# ADC_inputs.net
KiCad netlist of a schematic drawn in Altium Designer
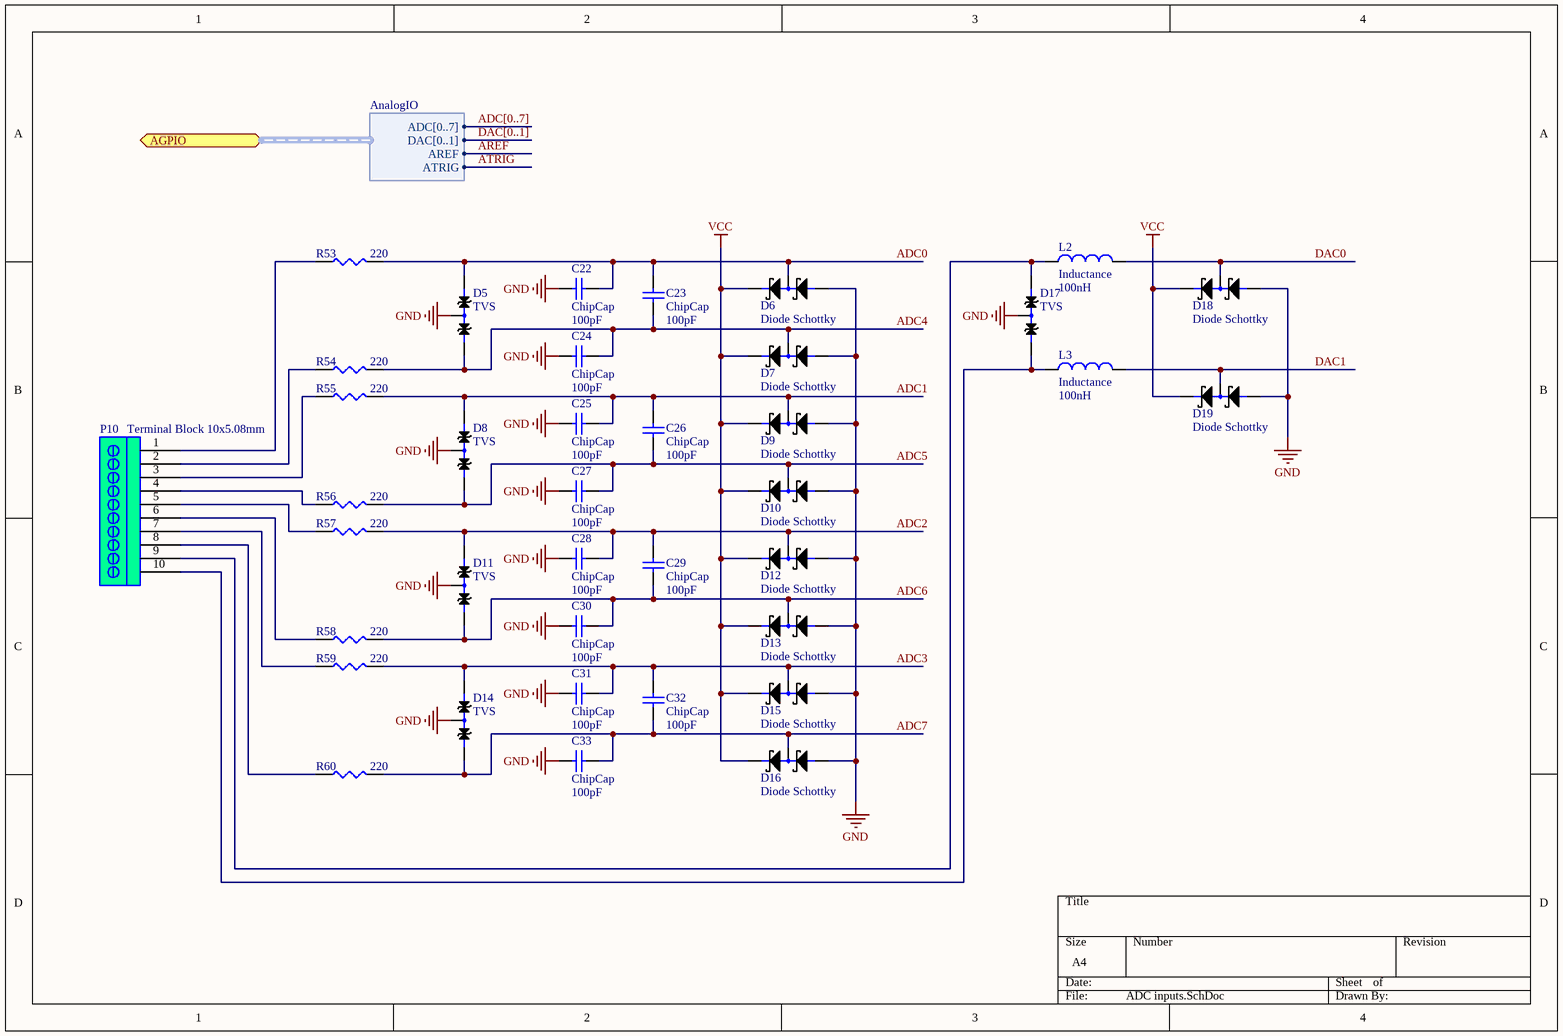
[diagram p0: ADC inputs.SchDoc]

(export (version "E")
  (design (tool "Eeschema 10.0.6"))
  (components
    (comp (ref "C22")
      (value "ChipCap")
      (footprint "CAP0805")
      (description "Capacitor")
      (fields (field (name "ALTIUM_VALUE") "100pF") (field (name "PUBLISHER") "Altium Limited"))
      (libsource (lib "Common Devices") (part "ChipCap"))
    )
    (comp (ref "C23")
      (value "ChipCap")
      (footprint "CAP0805")
      (description "Capacitor")
      (fields (field (name "ALTIUM_VALUE") "100pF") (field (name "PUBLISHER") "Altium Limited"))
      (libsource (lib "Common Devices") (part "ChipCap"))
    )
    (comp (ref "C24")
      (value "ChipCap")
      (footprint "CAP0805")
      (description "Capacitor")
      (fields (field (name "ALTIUM_VALUE") "100pF") (field (name "PUBLISHER") "Altium Limited"))
      (libsource (lib "Common Devices") (part "ChipCap"))
    )
    (comp (ref "C25")
      (value "ChipCap")
      (footprint "CAP0805")
      (description "Capacitor")
      (fields (field (name "ALTIUM_VALUE") "100pF") (field (name "PUBLISHER") "Altium Limited"))
      (libsource (lib "Common Devices") (part "ChipCap"))
    )
    (comp (ref "C26")
      (value "ChipCap")
      (footprint "CAP0805")
      (description "Capacitor")
      (fields (field (name "ALTIUM_VALUE") "100pF") (field (name "PUBLISHER") "Altium Limited"))
      (libsource (lib "Common Devices") (part "ChipCap"))
    )
    (comp (ref "C27")
      (value "ChipCap")
      (footprint "CAP0805")
      (description "Capacitor")
      (fields (field (name "ALTIUM_VALUE") "100pF") (field (name "PUBLISHER") "Altium Limited"))
      (libsource (lib "Common Devices") (part "ChipCap"))
    )
    (comp (ref "C28")
      (value "ChipCap")
      (footprint "CAP0805")
      (description "Capacitor")
      (fields (field (name "ALTIUM_VALUE") "100pF") (field (name "PUBLISHER") "Altium Limited"))
      (libsource (lib "Common Devices") (part "ChipCap"))
    )
    (comp (ref "C29")
      (value "ChipCap")
      (footprint "CAP0805")
      (description "Capacitor")
      (fields (field (name "ALTIUM_VALUE") "100pF") (field (name "PUBLISHER") "Altium Limited"))
      (libsource (lib "Common Devices") (part "ChipCap"))
    )
    (comp (ref "C30")
      (value "ChipCap")
      (footprint "CAP0805")
      (description "Capacitor")
      (fields (field (name "ALTIUM_VALUE") "100pF") (field (name "PUBLISHER") "Altium Limited"))
      (libsource (lib "Common Devices") (part "ChipCap"))
    )
    (comp (ref "C31")
      (value "ChipCap")
      (footprint "CAP0805")
      (description "Capacitor")
      (fields (field (name "ALTIUM_VALUE") "100pF") (field (name "PUBLISHER") "Altium Limited"))
      (libsource (lib "Common Devices") (part "ChipCap"))
    )
    (comp (ref "C32")
      (value "ChipCap")
      (footprint "CAP0805")
      (description "Capacitor")
      (fields (field (name "ALTIUM_VALUE") "100pF") (field (name "PUBLISHER") "Altium Limited"))
      (libsource (lib "Common Devices") (part "ChipCap"))
    )
    (comp (ref "C33")
      (value "ChipCap")
      (footprint "CAP0805")
      (description "Capacitor")
      (fields (field (name "ALTIUM_VALUE") "100pF") (field (name "PUBLISHER") "Altium Limited"))
      (libsource (lib "Common Devices") (part "ChipCap"))
    )
    (comp (ref "D5")
      (value "TVS")
      (footprint "SOT23")
      (description "Dual bidirectional voltage supresor")
      (libsource (lib "Protection") (part "TVS Diode"))
    )
    (comp (ref "D6")
      (value "Diode Schottky")
      (footprint "SOT23")
      (description "2-Diode Schottky")
      (libsource (lib "Protection") (part "Schottky Diode"))
    )
    (comp (ref "D7")
      (value "Diode Schottky")
      (footprint "SOT23")
      (description "2-Diode Schottky")
      (libsource (lib "Protection") (part "Schottky Diode"))
    )
    (comp (ref "D8")
      (value "TVS")
      (footprint "SOT23")
      (description "Dual bidirectional voltage supresor")
      (libsource (lib "Protection") (part "TVS Diode"))
    )
    (comp (ref "D9")
      (value "Diode Schottky")
      (footprint "SOT23")
      (description "2-Diode Schottky")
      (libsource (lib "Protection") (part "Schottky Diode"))
    )
    (comp (ref "D10")
      (value "Diode Schottky")
      (footprint "SOT23")
      (description "2-Diode Schottky")
      (libsource (lib "Protection") (part "Schottky Diode"))
    )
    (comp (ref "D11")
      (value "TVS")
      (footprint "SOT23")
      (description "Dual bidirectional voltage supresor")
      (libsource (lib "Protection") (part "TVS Diode"))
    )
    (comp (ref "D12")
      (value "Diode Schottky")
      (footprint "SOT23")
      (description "2-Diode Schottky")
      (libsource (lib "Protection") (part "Schottky Diode"))
    )
    (comp (ref "D13")
      (value "Diode Schottky")
      (footprint "SOT23")
      (description "2-Diode Schottky")
      (libsource (lib "Protection") (part "Schottky Diode"))
    )
    (comp (ref "D14")
      (value "TVS")
      (footprint "SOT23")
      (description "Dual bidirectional voltage supresor")
      (libsource (lib "Protection") (part "TVS Diode"))
    )
    (comp (ref "D15")
      (value "Diode Schottky")
      (footprint "SOT23")
      (description "2-Diode Schottky")
      (libsource (lib "Protection") (part "Schottky Diode"))
    )
    (comp (ref "D16")
      (value "Diode Schottky")
      (footprint "SOT23")
      (description "2-Diode Schottky")
      (libsource (lib "Protection") (part "Schottky Diode"))
    )
    (comp (ref "D17")
      (value "TVS")
      (footprint "SOT23")
      (description "Dual bidirectional voltage supresor")
      (libsource (lib "Protection") (part "TVS Diode"))
    )
    (comp (ref "D18")
      (value "Diode Schottky")
      (footprint "SOT23")
      (description "2-Diode Schottky")
      (libsource (lib "Protection") (part "Schottky Diode"))
    )
    (comp (ref "D19")
      (value "Diode Schottky")
      (footprint "SOT23")
      (description "2-Diode Schottky")
      (libsource (lib "Protection") (part "Schottky Diode"))
    )
    (comp (ref "L2")
      (value "Inductance")
      (footprint "CM45")
      (fields (field (name "ALTIUM_VALUE") "100nH"))
      (libsource (lib "Common Devices") (part "ChipInductance"))
    )
    (comp (ref "L3")
      (value "Inductance")
      (footprint "CM45")
      (fields (field (name "ALTIUM_VALUE") "100nH"))
      (libsource (lib "Common Devices") (part "ChipInductance"))
    )
    (comp (ref "P10")
      (value "Terminal Block 10x5.08mm")
      (footprint "Socket 10x5.08")
      (description "Terminal Block Socket Right Angle 10x5.08mm 2-Wall")
      (libsource (lib "IndustrialConnectors") (part "Socket_10x5.08_RA_2Wall"))
    )
    (comp (ref "R53")
      (value "220")
      (footprint "RES0805")
      (description "Chip resistor")
      (fields (field (name "Comment") "ChipRes"))
      (libsource (lib "Common Devices") (part "ChipRes"))
    )
    (comp (ref "R54")
      (value "220")
      (footprint "RES0805")
      (description "Chip resistor")
      (fields (field (name "Comment") "ChipRes"))
      (libsource (lib "Common Devices") (part "ChipRes"))
    )
    (comp (ref "R55")
      (value "220")
      (footprint "RES0805")
      (description "Chip resistor")
      (fields (field (name "Comment") "ChipRes"))
      (libsource (lib "Common Devices") (part "ChipRes"))
    )
    (comp (ref "R56")
      (value "220")
      (footprint "RES0805")
      (description "Chip resistor")
      (fields (field (name "Comment") "ChipRes"))
      (libsource (lib "Common Devices") (part "ChipRes"))
    )
    (comp (ref "R57")
      (value "220")
      (footprint "RES0805")
      (description "Chip resistor")
      (fields (field (name "Comment") "ChipRes"))
      (libsource (lib "Common Devices") (part "ChipRes"))
    )
    (comp (ref "R58")
      (value "220")
      (footprint "RES0805")
      (description "Chip resistor")
      (fields (field (name "Comment") "ChipRes"))
      (libsource (lib "Common Devices") (part "ChipRes"))
    )
    (comp (ref "R59")
      (value "220")
      (footprint "RES0805")
      (description "Chip resistor")
      (fields (field (name "Comment") "ChipRes"))
      (libsource (lib "Common Devices") (part "ChipRes"))
    )
    (comp (ref "R60")
      (value "220")
      (footprint "RES0805")
      (description "Chip resistor")
      (fields (field (name "Comment") "ChipRes"))
      (libsource (lib "Common Devices") (part "ChipRes"))
    )
  )
  (nets
    (net (code "2") (name "/ADC0") (class "Default")
      (node (ref "C22") (pin "1") (pinfunction "1_1") (pintype "passive"))
      (node (ref "C23") (pin "2") (pinfunction "2_2") (pintype "passive"))
      (node (ref "D5") (pin "1") (pinfunction "1_1") (pintype "passive"))
      (node (ref "D6") (pin "3") (pinfunction "3_3") (pintype "passive"))
      (node (ref "R53") (pin "2") (pintype "passive"))
    )
    (net (code "3") (name "/ADC1") (class "Default")
      (node (ref "C25") (pin "1") (pinfunction "1_1") (pintype "passive"))
      (node (ref "C26") (pin "2") (pinfunction "2_2") (pintype "passive"))
      (node (ref "D8") (pin "1") (pinfunction "1_1") (pintype "passive"))
      (node (ref "D9") (pin "3") (pinfunction "3_3") (pintype "passive"))
      (node (ref "R55") (pin "2") (pintype "passive"))
    )
    (net (code "4") (name "/ADC2") (class "Default")
      (node (ref "C28") (pin "1") (pinfunction "1_1") (pintype "passive"))
      (node (ref "C29") (pin "2") (pinfunction "2_2") (pintype "passive"))
      (node (ref "D11") (pin "1") (pinfunction "1_1") (pintype "passive"))
      (node (ref "D12") (pin "3") (pinfunction "3_3") (pintype "passive"))
      (node (ref "R57") (pin "2") (pintype "passive"))
    )
    (net (code "5") (name "/ADC3") (class "Default")
      (node (ref "C31") (pin "1") (pinfunction "1_1") (pintype "passive"))
      (node (ref "C32") (pin "2") (pinfunction "2_2") (pintype "passive"))
      (node (ref "D14") (pin "1") (pinfunction "1_1") (pintype "passive"))
      (node (ref "D15") (pin "3") (pinfunction "3_3") (pintype "passive"))
      (node (ref "R59") (pin "2") (pintype "passive"))
    )
    (net (code "6") (name "/ADC4") (class "Default")
      (node (ref "C23") (pin "1") (pinfunction "1_1") (pintype "passive"))
      (node (ref "C24") (pin "1") (pinfunction "1_1") (pintype "passive"))
      (node (ref "D5") (pin "2") (pinfunction "2_2") (pintype "passive"))
      (node (ref "D7") (pin "3") (pinfunction "3_3") (pintype "passive"))
      (node (ref "R54") (pin "2") (pintype "passive"))
    )
    (net (code "7") (name "/ADC5") (class "Default")
      (node (ref "C26") (pin "1") (pinfunction "1_1") (pintype "passive"))
      (node (ref "C27") (pin "1") (pinfunction "1_1") (pintype "passive"))
      (node (ref "D10") (pin "3") (pinfunction "3_3") (pintype "passive"))
      (node (ref "D8") (pin "2") (pinfunction "2_2") (pintype "passive"))
      (node (ref "R56") (pin "2") (pintype "passive"))
    )
    (net (code "8") (name "/ADC6") (class "Default")
      (node (ref "C29") (pin "1") (pinfunction "1_1") (pintype "passive"))
      (node (ref "C30") (pin "1") (pinfunction "1_1") (pintype "passive"))
      (node (ref "D11") (pin "2") (pinfunction "2_2") (pintype "passive"))
      (node (ref "D13") (pin "3") (pinfunction "3_3") (pintype "passive"))
      (node (ref "R58") (pin "2") (pintype "passive"))
    )
    (net (code "9") (name "/ADC7") (class "Default")
      (node (ref "C32") (pin "1") (pinfunction "1_1") (pintype "passive"))
      (node (ref "C33") (pin "1") (pinfunction "1_1") (pintype "passive"))
      (node (ref "D14") (pin "2") (pinfunction "2_2") (pintype "passive"))
      (node (ref "D16") (pin "3") (pinfunction "3_3") (pintype "passive"))
      (node (ref "R60") (pin "2") (pintype "passive"))
    )
    (net (code "13") (name "/DAC0") (class "Default")
      (node (ref "D18") (pin "3") (pinfunction "3_3") (pintype "passive"))
      (node (ref "L2") (pin "1") (pintype "passive"))
    )
    (net (code "14") (name "/DAC1") (class "Default")
      (node (ref "D19") (pin "3") (pinfunction "3_3") (pintype "passive"))
      (node (ref "L3") (pin "1") (pintype "passive"))
    )
    (net (code "17") (name "GND") (class "Default")
      (node (ref "C22") (pin "2") (pinfunction "2_2") (pintype "passive"))
      (node (ref "C24") (pin "2") (pinfunction "2_2") (pintype "passive"))
      (node (ref "C25") (pin "2") (pinfunction "2_2") (pintype "passive"))
      (node (ref "C27") (pin "2") (pinfunction "2_2") (pintype "passive"))
      (node (ref "C28") (pin "2") (pinfunction "2_2") (pintype "passive"))
      (node (ref "C30") (pin "2") (pinfunction "2_2") (pintype "passive"))
      (node (ref "C31") (pin "2") (pinfunction "2_2") (pintype "passive"))
      (node (ref "C33") (pin "2") (pinfunction "2_2") (pintype "passive"))
      (node (ref "D10") (pin "1") (pinfunction "1_1") (pintype "passive"))
      (node (ref "D11") (pin "3") (pinfunction "3_3") (pintype "passive"))
      (node (ref "D12") (pin "1") (pinfunction "1_1") (pintype "passive"))
      (node (ref "D13") (pin "1") (pinfunction "1_1") (pintype "passive"))
      (node (ref "D14") (pin "3") (pinfunction "3_3") (pintype "passive"))
      (node (ref "D15") (pin "1") (pinfunction "1_1") (pintype "passive"))
      (node (ref "D16") (pin "1") (pinfunction "1_1") (pintype "passive"))
      (node (ref "D17") (pin "3") (pinfunction "3_3") (pintype "passive"))
      (node (ref "D18") (pin "1") (pinfunction "1_1") (pintype "passive"))
      (node (ref "D19") (pin "1") (pinfunction "1_1") (pintype "passive"))
      (node (ref "D5") (pin "3") (pinfunction "3_3") (pintype "passive"))
      (node (ref "D6") (pin "1") (pinfunction "1_1") (pintype "passive"))
      (node (ref "D7") (pin "1") (pinfunction "1_1") (pintype "passive"))
      (node (ref "D8") (pin "3") (pinfunction "3_3") (pintype "passive"))
      (node (ref "D9") (pin "1") (pinfunction "1_1") (pintype "passive"))
    )
    (net (code "18") (name "Net-(D17-Pad1)") (class "Default")
      (node (ref "D17") (pin "1") (pinfunction "1_1") (pintype "passive"))
      (node (ref "L2") (pin "2") (pintype "passive"))
      (node (ref "P10") (pin "9") (pintype "passive"))
    )
    (net (code "19") (name "Net-(D17-Pad2)") (class "Default")
      (node (ref "D17") (pin "2") (pinfunction "2_2") (pintype "passive"))
      (node (ref "L3") (pin "2") (pintype "passive"))
      (node (ref "P10") (pin "10") (pintype "passive"))
    )
    (net (code "20") (name "Net-(P10-Pad1)") (class "Default")
      (node (ref "P10") (pin "1") (pintype "passive"))
      (node (ref "R53") (pin "1") (pintype "passive"))
    )
    (net (code "21") (name "Net-(P10-Pad2)") (class "Default")
      (node (ref "P10") (pin "2") (pintype "passive"))
      (node (ref "R54") (pin "1") (pintype "passive"))
    )
    (net (code "22") (name "Net-(P10-Pad3)") (class "Default")
      (node (ref "P10") (pin "3") (pintype "passive"))
      (node (ref "R55") (pin "1") (pintype "passive"))
    )
    (net (code "23") (name "Net-(P10-Pad4)") (class "Default")
      (node (ref "P10") (pin "4") (pintype "passive"))
      (node (ref "R56") (pin "1") (pintype "passive"))
    )
    (net (code "24") (name "Net-(P10-Pad5)") (class "Default")
      (node (ref "P10") (pin "5") (pintype "passive"))
      (node (ref "R57") (pin "1") (pintype "passive"))
    )
    (net (code "25") (name "Net-(P10-Pad6)") (class "Default")
      (node (ref "P10") (pin "6") (pintype "passive"))
      (node (ref "R58") (pin "1") (pintype "passive"))
    )
    (net (code "26") (name "Net-(P10-Pad7)") (class "Default")
      (node (ref "P10") (pin "7") (pintype "passive"))
      (node (ref "R59") (pin "1") (pintype "passive"))
    )
    (net (code "27") (name "Net-(P10-Pad8)") (class "Default")
      (node (ref "P10") (pin "8") (pintype "passive"))
      (node (ref "R60") (pin "1") (pintype "passive"))
    )
    (net (code "28") (name "VCC") (class "Default")
      (node (ref "D10") (pin "2") (pinfunction "2_2") (pintype "passive"))
      (node (ref "D12") (pin "2") (pinfunction "2_2") (pintype "passive"))
      (node (ref "D13") (pin "2") (pinfunction "2_2") (pintype "passive"))
      (node (ref "D15") (pin "2") (pinfunction "2_2") (pintype "passive"))
      (node (ref "D16") (pin "2") (pinfunction "2_2") (pintype "passive"))
      (node (ref "D18") (pin "2") (pinfunction "2_2") (pintype "passive"))
      (node (ref "D19") (pin "2") (pinfunction "2_2") (pintype "passive"))
      (node (ref "D6") (pin "2") (pinfunction "2_2") (pintype "passive"))
      (node (ref "D7") (pin "2") (pinfunction "2_2") (pintype "passive"))
      (node (ref "D9") (pin "2") (pinfunction "2_2") (pintype "passive"))
    )
  )
)
